# 5v_BOOST.net
KiCad netlist of a schematic drawn in Altium Designer
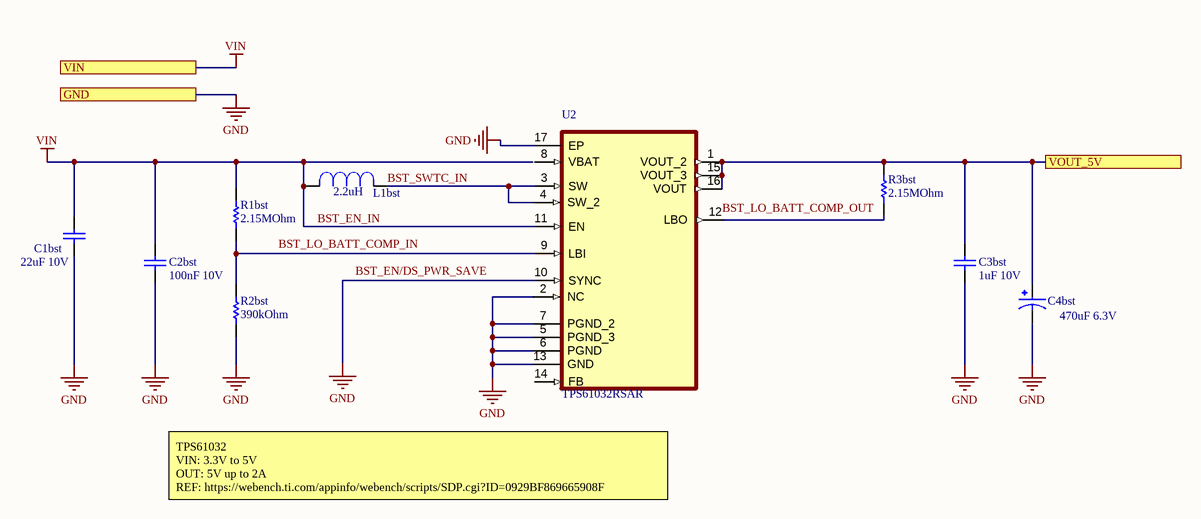
[diagram p0: 5v_BOOST.SchDoc]

(export (version "E")
  (design (tool "Eeschema 10.0.6"))
  (components
    (comp (ref "C1bst")
      (value "22uF 10V")
      (footprint "CAPC1608X100X20ML10")
      (description "Chip Capacitor, 22 uF, +/- 20%, 10 V, -55 to 85 degC, 0603 (1608 Metric), RoHS, Tape and Reel")
      (fields (field (name "MANUFACTURER") "TDK") (field (name "TOLERANCE") "±20%"))
      (libsource (lib "Altium Content Vault") (part "CAP-NP-2"))
    )
    (comp (ref "C2bst")
      (value "100nF 10V")
      (footprint "CAPC1005X55X25LL05T10")
      (fields (field (name "MANUFACTURER") "Murata"))
      (libsource (lib "Altium Content Vault") (part "CAP-NP-2"))
    )
    (comp (ref "C3bst")
      (value "1uF 10V")
      (footprint "CAPC1608X90X35LL15T15")
      (description "0603(1608) C0603C105K8PACTU")
      (fields (field (name "PART NUMBER") "C0603C105K8PACTU") (field (name "MANUFACTURER") "Kemet"))
      (libsource (lib "Altium Content Vault") (part "CAP"))
    )
    (comp (ref "C4bst")
      (value "470uF 6.3V")
      (footprint "6TPB470M")
      (fields
        (field (name "MP") "6TPB470M")
        (field (name "MANUFACTURER") "Panasonic")
        (field (name "TOLERANCE") "20%")
      )
      (libsource (lib "CommonComponents_DIY") (part "6TPB470M"))
    )
    (comp (ref "L1bst")
      (value "2.2uH")
      (footprint "DR127-2R2-R")
      (description "Ind Power Shielded Wirewound 2.2uH 20% 100KHz Ferrite 12.5A T/R DR127-2R2-R")
      (fields (field (name "MP") "DR127-2R2-R") (field (name "MF") "Eaton"))
      (libsource (lib "CommonComponents_DIY") (part "DR127-2R2-R"))
    )
    (comp (ref "R1bst")
      (value "2.15MOhm")
      (footprint "RESC1005X40X25LL05T05")
      (description "1% 0402(1005)CRCW04022M15FKED")
      (fields (field (name "MANUFACTURER") "Vishay Dale") (field (name "PART NUMBER") "CRCW04022M15FKED"))
      (libsource (lib "Altium Content Vault") (part "RES"))
    )
    (comp (ref "R2bst")
      (value "390kOhm")
      (footprint "RESC0603(1608)_L")
      (description "390K 0.1W 1% 0603 (1608 Metric)  SMD")
      (fields (field (name "POWER") "0.1 W") (field (name "TOLERANCE") "1 %"))
      (libsource (lib "Altium Content Vault") (part "RES"))
    )
    (comp (ref "R3bst")
      (value "2.15MOhm")
      (footprint "RESC1005X40X25LL05T05")
      (description "1% 0402(1005) CRCW04022M15FKED")
      (fields (field (name "MANUFACTURER") "Vishay Dale") (field (name "PART NUMBER") "CRCW04022M15FKED"))
      (libsource (lib "Altium Content Vault") (part "RES"))
    )
    (comp (ref "U2")
      (value "TPS61032RSAR")
      (footprint "TPS61032RSAR")
      (description "5-V Output, 1-A, 96% Efficient Boost Converter w/20uA Iq in TSSOP-16 16-QFN -40 to 85")
      (fields (field (name "MANUFACTURER") "Texas Instruments"))
      (libsource (lib "CommonComponents_DIY") (part "TPS61032RSAR"))
    )
  )
  (nets
    (net (code "4") (name "/BST_SWTC_IN") (class "Default")
      (node (ref "L1bst") (pin "1") (pinfunction "1_1") (pintype "passive"))
      (node (ref "U2") (pin "3") (pinfunction "SW_3") (pintype "input"))
      (node (ref "U2") (pin "4") (pinfunction "SW_2_4") (pintype "input"))
    )
    (net (code "5") (name "/VOUT_5V") (class "Default")
      (node (ref "C3bst") (pin "2") (pinfunction "2_2") (pintype "passive"))
      (node (ref "C4bst") (pin "1") (pinfunction "1_1") (pintype "passive"))
      (node (ref "R3bst") (pin "2") (pinfunction "2_2") (pintype "passive"))
      (node (ref "U2") (pin "1") (pinfunction "VOUT_2_1") (pintype "output"))
      (node (ref "U2") (pin "15") (pinfunction "VOUT_3_15") (pintype "output"))
      (node (ref "U2") (pin "16") (pinfunction "VOUT_16") (pintype "output"))
    )
    (net (code "6") (name "GND") (class "Default")
      (node (ref "C1bst") (pin "1") (pinfunction "1_1") (pintype "passive"))
      (node (ref "C2bst") (pin "1") (pinfunction "1_1") (pintype "passive"))
      (node (ref "C3bst") (pin "1") (pinfunction "1_1") (pintype "passive"))
      (node (ref "C4bst") (pin "2") (pinfunction "2_2") (pintype "passive"))
      (node (ref "R2bst") (pin "1") (pinfunction "1_1") (pintype "passive"))
      (node (ref "U2") (pin "10") (pinfunction "SYNC_10") (pintype "input"))
      (node (ref "U2") (pin "13") (pinfunction "GND_13") (pintype "passive"))
      (node (ref "U2") (pin "17") (pinfunction "EP_17") (pintype "passive"))
      (node (ref "U2") (pin "2") (pinfunction "NC_2") (pintype "input"))
      (node (ref "U2") (pin "5") (pinfunction "PGND_3_5") (pintype "passive"))
      (node (ref "U2") (pin "6") (pinfunction "PGND_6") (pintype "passive"))
      (node (ref "U2") (pin "7") (pinfunction "PGND_2_7") (pintype "passive"))
    )
    (net (code "7") (name "Net-(U2-LBI)") (class "Default")
      (node (ref "R1bst") (pin "1") (pinfunction "1_1") (pintype "passive"))
      (node (ref "R2bst") (pin "2") (pinfunction "2_2") (pintype "passive"))
      (node (ref "U2") (pin "9") (pinfunction "LBI_9") (pintype "input"))
    )
    (net (code "8") (name "Net-(U2-LBO)") (class "Default")
      (node (ref "R3bst") (pin "1") (pinfunction "1_1") (pintype "passive"))
      (node (ref "U2") (pin "12") (pinfunction "LBO_12") (pintype "output"))
    )
    (net (code "9") (name "VIN") (class "Default")
      (node (ref "C1bst") (pin "2") (pinfunction "2_2") (pintype "passive"))
      (node (ref "C2bst") (pin "2") (pinfunction "2_2") (pintype "passive"))
      (node (ref "L1bst") (pin "2") (pinfunction "2_2") (pintype "passive"))
      (node (ref "R1bst") (pin "2") (pinfunction "2_2") (pintype "passive"))
      (node (ref "U2") (pin "11") (pinfunction "EN_11") (pintype "input"))
    )
    (net (code "10") (name "unconnected-(U2-FB-Pad14)") (class "Default")
      (node (ref "U2") (pin "14") (pinfunction "FB_14") (pintype "input"))
    )
    (net (code "11") (name "unconnected-(U2-VBAT-Pad8)") (class "Default")
      (node (ref "U2") (pin "8") (pinfunction "VBAT_8") (pintype "input"))
    )
  )
)
